# current_monitor_v1-2-1.net
KiCad netlist of a schematic drawn in EAGLE
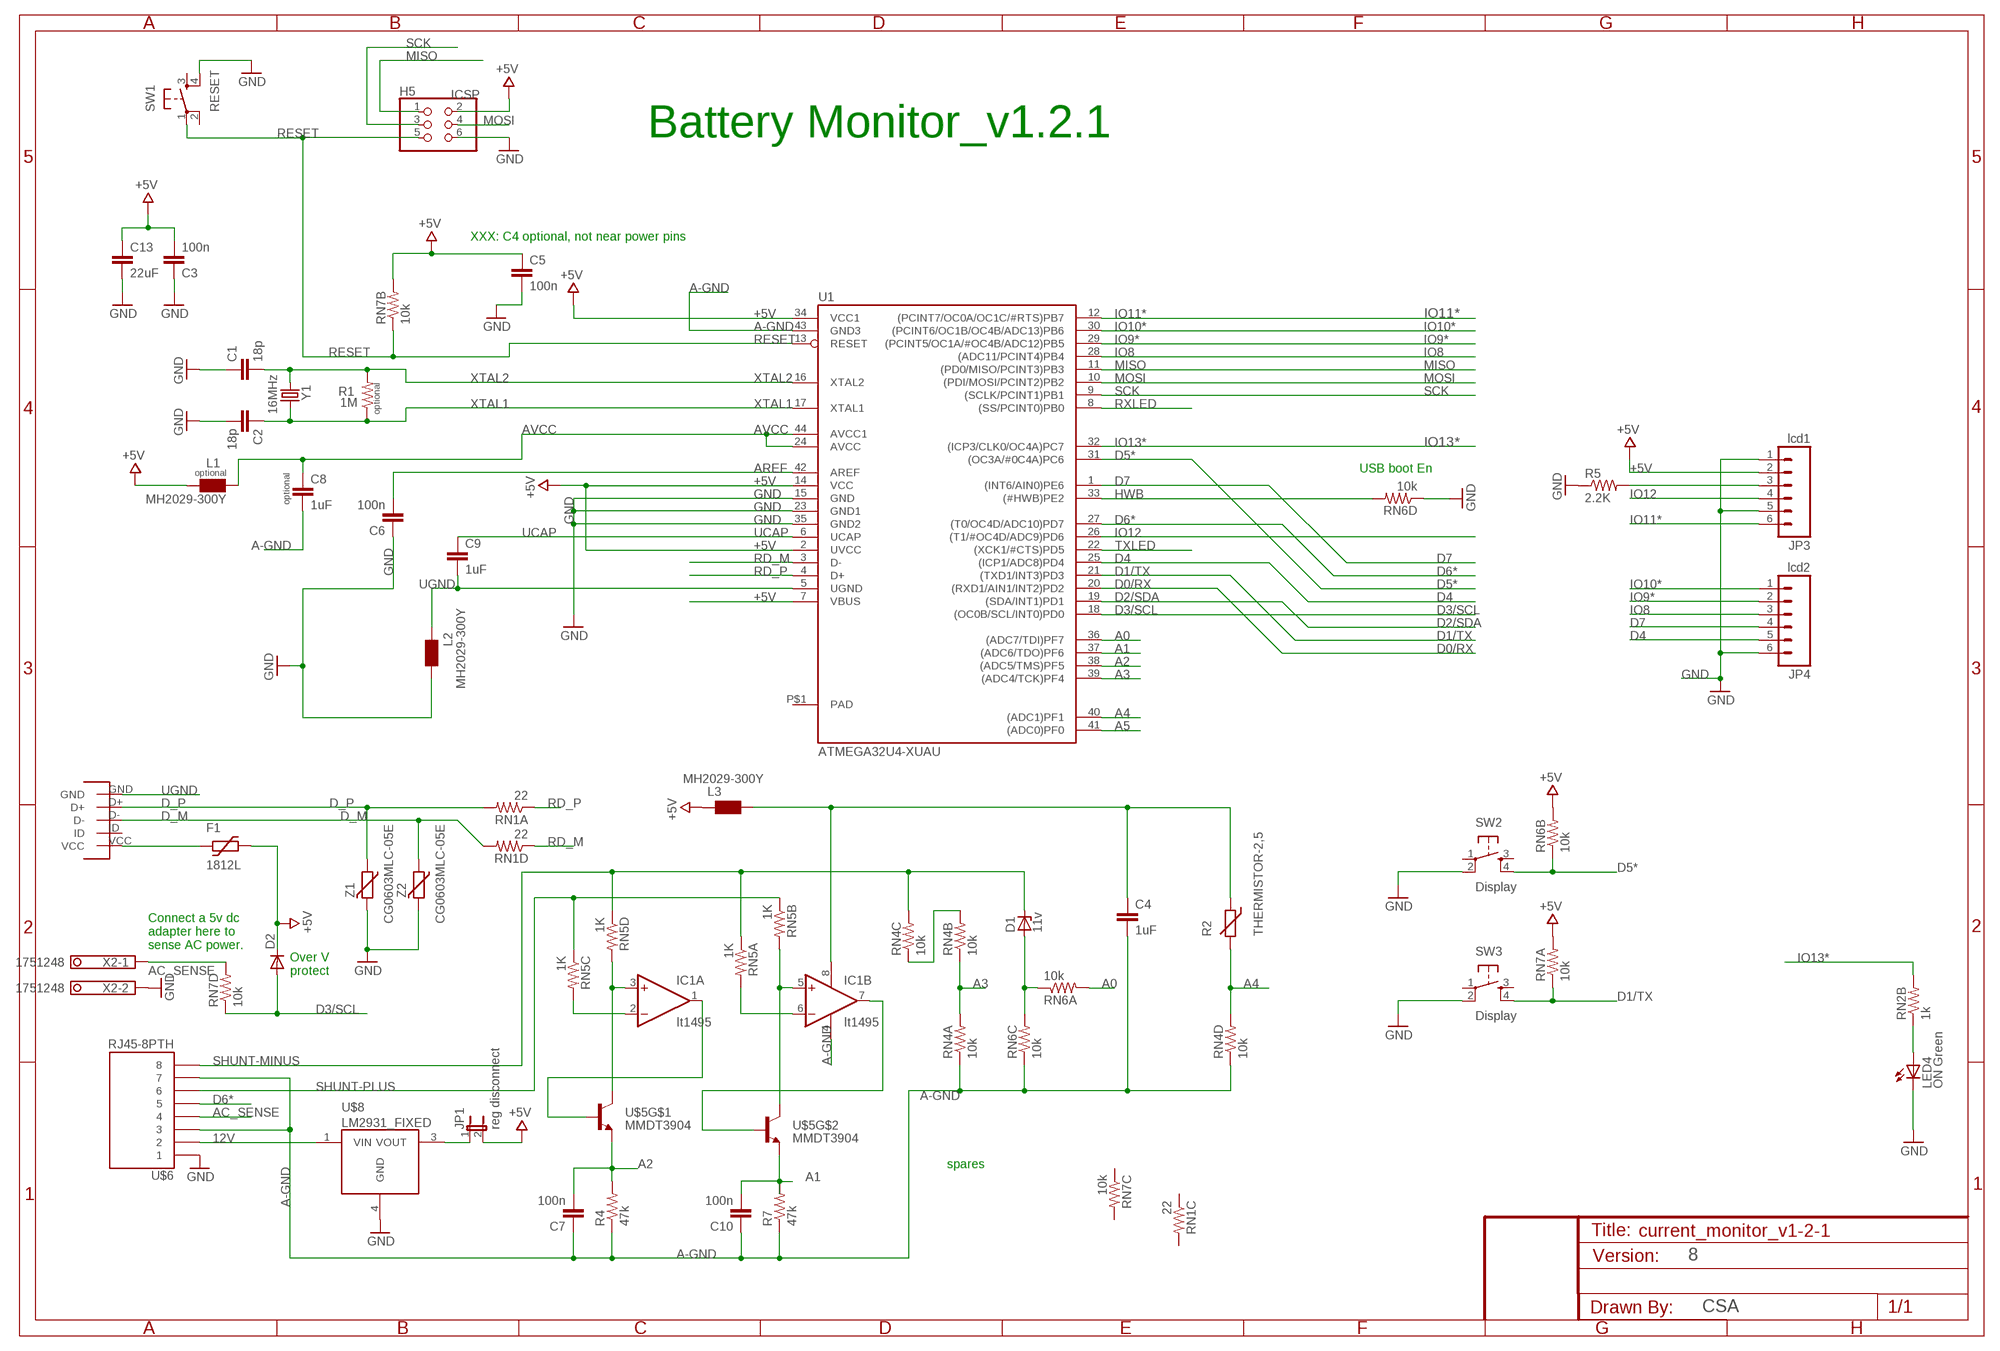
[diagram p0: schematic, sheet 1]

(export (version "E")
  (design (tool "Eeschema 10.0.6"))
  (components
    (comp (ref "C1")
      (value "18p")
      (footprint "eagle-import:0805")
      (libsource (lib "eagle-import") (part "CAP0805"))
    )
    (comp (ref "C2")
      (value "18p")
      (footprint "eagle-import:0805")
      (libsource (lib "eagle-import") (part "CAP0805"))
    )
    (comp (ref "C3")
      (value "100n")
      (footprint "eagle-import:0805")
      (libsource (lib "eagle-import") (part "CAP0805"))
    )
    (comp (ref "C4")
      (value "1uF")
      (footprint "eagle-import:0805")
      (libsource (lib "eagle-import") (part "CAP0805"))
    )
    (comp (ref "C5")
      (value "100n")
      (footprint "eagle-import:0805")
      (libsource (lib "eagle-import") (part "CAP0805"))
    )
    (comp (ref "C6")
      (value "100n")
      (footprint "eagle-import:0805")
      (libsource (lib "eagle-import") (part "CAP0805"))
    )
    (comp (ref "C7")
      (value "100n")
      (footprint "eagle-import:0805")
      (libsource (lib "eagle-import") (part "CAP0805"))
    )
    (comp (ref "C8")
      (value "1uF")
      (footprint "eagle-import:0805")
      (libsource (lib "eagle-import") (part "CAP0805"))
    )
    (comp (ref "C9")
      (value "1uF")
      (footprint "eagle-import:0805")
      (libsource (lib "eagle-import") (part "CAP0805"))
    )
    (comp (ref "C10")
      (value "100n")
      (footprint "eagle-import:0805")
      (libsource (lib "eagle-import") (part "CAP0805"))
    )
    (comp (ref "C13")
      (value "22uF")
      (footprint "eagle-import:1206")
      (libsource (lib "eagle-import") (part "CAP1206"))
    )
    (comp (ref "D1")
      (value "11v")
      (footprint "eagle-import:ZDIO-5")
      (libsource (lib "eagle-import") (part "ZENER-DIODEZD-5"))
    )
    (comp (ref "D2")
      (value "DIODESMA")
      (footprint "eagle-import:SMA-DIODE")
      (libsource (lib "eagle-import") (part "DIODESMA"))
    )
    (comp (ref "F1")
      (value "1812L")
      (footprint "eagle-import:1812L")
      (libsource (lib "eagle-import") (part "1812L"))
    )
    (comp (ref "H5")
      (value "ICSP")
      (footprint "eagle-import:2X03")
      (libsource (lib "eagle-import") (part "PINHD-2X3"))
    )
    (comp (ref "IC1")
      (value "lt1495")
      (footprint "eagle-import:SO08")
      (libsource (lib "eagle-import") (part "4558DLM"))
    )
    (comp (ref "JP1")
      (value "reg disconnect")
      (footprint "eagle-import:1X02_LOCK")
      (libsource (lib "eagle-import") (part "JUMPER-2-OLDPTH_LOCK"))
    )
    (comp (ref "JP3")
      (value "lcd1")
      (footprint "eagle-import:1X06_FEMALE_LOCK.010")
      (libsource (lib "eagle-import") (part "M06FEMALE_LOCK"))
    )
    (comp (ref "JP4")
      (value "lcd2")
      (footprint "eagle-import:1X06_FEMALE_LOCK.010")
      (libsource (lib "eagle-import") (part "M06FEMALE_LOCK"))
    )
    (comp (ref "L1")
      (value "MH2029-300Y")
      (footprint "eagle-import:0805")
      (libsource (lib "eagle-import") (part "WE-CBF_0805"))
    )
    (comp (ref "L2")
      (value "MH2029-300Y")
      (footprint "eagle-import:0805")
      (libsource (lib "eagle-import") (part "WE-CBF_0805"))
    )
    (comp (ref "L3")
      (value "MH2029-300Y")
      (footprint "eagle-import:0805")
      (libsource (lib "eagle-import") (part "WE-CBF_0805"))
    )
    (comp (ref "LED4")
      (value "ON Green")
      (footprint "eagle-import:LED0805")
      (libsource (lib "eagle-import") (part "LED0805"))
    )
    (comp (ref "R1")
      (value "1M")
      (footprint "eagle-import:0805")
      (libsource (lib "eagle-import") (part "RESISTOR0805-RES"))
    )
    (comp (ref "R2")
      (value "THERMISTOR-2,5")
      (footprint "eagle-import:RS-2,5")
      (libsource (lib "eagle-import") (part "THERMISTOR-2,5"))
    )
    (comp (ref "R4")
      (value "47k")
      (footprint "eagle-import:0805")
      (libsource (lib "eagle-import") (part "RESISTOR0805-RES"))
    )
    (comp (ref "R5")
      (value "2.2K")
      (footprint "eagle-import:0805")
      (libsource (lib "eagle-import") (part "RESISTOR0805-RES"))
    )
    (comp (ref "R7")
      (value "47k")
      (footprint "eagle-import:0805")
      (libsource (lib "eagle-import") (part "RESISTOR0805-RES"))
    )
    (comp (ref "RN1")
      (value "22")
      (footprint "eagle-import:CRA06S")
      (libsource (lib "eagle-import") (part "RESISTOR-ARRAYCRA06S"))
    )
    (comp (ref "RN2")
      (value "1k")
      (footprint "eagle-import:CRA06S")
      (libsource (lib "eagle-import") (part "RESISTOR-ARRAYCRA06S"))
    )
    (comp (ref "RN4")
      (value "10k")
      (footprint "eagle-import:CRA06S")
      (libsource (lib "eagle-import") (part "RESISTOR-ARRAYCRA06S"))
    )
    (comp (ref "RN5")
      (value "1K")
      (footprint "eagle-import:CRA06S")
      (libsource (lib "eagle-import") (part "RESISTOR-ARRAYCRA06S"))
    )
    (comp (ref "RN6")
      (value "10k")
      (footprint "eagle-import:CRA06S")
      (libsource (lib "eagle-import") (part "RESISTOR-ARRAYCRA06S"))
    )
    (comp (ref "RN7")
      (value "10k")
      (footprint "eagle-import:CRA06S")
      (libsource (lib "eagle-import") (part "RESISTOR-ARRAYCRA06S"))
    )
    (comp (ref "SW1")
      (value "RESET")
      (footprint "eagle-import:TACTILE-PTH")
      (libsource (lib "eagle-import") (part "TAC_SWITCHPTH"))
    )
    (comp (ref "SW2")
      (value "Display")
      (footprint "eagle-import:TACTILE-PTH")
      (libsource (lib "eagle-import") (part "TAC_SWITCHPTH"))
    )
    (comp (ref "SW3")
      (value "Display")
      (footprint "eagle-import:TACTILE-PTH")
      (libsource (lib "eagle-import") (part "TAC_SWITCHPTH"))
    )
    (comp (ref "U$5")
      (value "MMDT3904")
      (footprint "eagle-import:SOT363")
      (libsource (lib "eagle-import") (part "MMDT3904"))
    )
    (comp (ref "U$6")
      (value "RJ45-8PTH")
      (footprint "eagle-import:RJ45-8")
      (libsource (lib "eagle-import") (part "RJ45-8PTH"))
    )
    (comp (ref "U$8")
      (value "LM2931_FIXED")
      (footprint "eagle-import:DPAK")
      (libsource (lib "eagle-import") (part "LM2931_FIXED"))
    )
    (comp (ref "U$16")
      (value "USB-MICRO-B-DIGIKEY")
      (footprint "eagle-import:USB-MICRO-B-DIGIKEY")
      (libsource (lib "eagle-import") (part "USB-MICRO-B-DIGIKEY"))
    )
    (comp (ref "U1")
      (value "ATMEGA32U4-XUAU")
      (footprint "eagle-import:TQFP44-PAD")
      (libsource (lib "eagle-import") (part "ATMEGA32U4-XUAU"))
    )
    (comp (ref "X2")
      (value "1751248")
      (footprint "eagle-import:1751248")
      (libsource (lib "eagle-import") (part "1751248"))
    )
    (comp (ref "Y1")
      (value "16MHz")
      (footprint "eagle-import:HC49US")
      (libsource (lib "eagle-import") (part "CRYSTALHC49US"))
    )
    (comp (ref "Z1")
      (value "CG0603MLC-05E")
      (footprint "eagle-import:CT_CN0603")
      (libsource (lib "eagle-import") (part "VARISTORCN0603"))
    )
    (comp (ref "Z2")
      (value "CG0603MLC-05E")
      (footprint "eagle-import:CT_CN0603")
      (libsource (lib "eagle-import") (part "VARISTORCN0603"))
    )
  )
  (nets
    (net (code "1") (name "+5V") (class "Default")
      (node (ref "C13") (pin "1") (pinfunction "1_1") (pintype "passive"))
      (node (ref "C3") (pin "2") (pinfunction "2_2") (pintype "passive"))
      (node (ref "C5") (pin "1") (pinfunction "1_1") (pintype "passive"))
      (node (ref "D2") (pin "C") (pinfunction "C_C") (pintype "passive"))
      (node (ref "F1") (pin "P$2") (pinfunction "2_P$2") (pintype "passive"))
      (node (ref "H5") (pin "2") (pinfunction "2_2") (pintype "passive"))
      (node (ref "JP1") (pin "2") (pinfunction "2_2") (pintype "passive"))
      (node (ref "JP3") (pin "2") (pinfunction "2_2") (pintype "passive"))
      (node (ref "L1") (pin "1") (pinfunction "1_1") (pintype "passive"))
      (node (ref "L3") (pin "1") (pinfunction "1_1") (pintype "passive"))
      (node (ref "RN6") (pin "7") (pinfunction "2_7") (pintype "passive"))
      (node (ref "RN7") (pin "7") (pinfunction "2_7") (pintype "passive"))
      (node (ref "RN7") (pin "8") (pinfunction "2_8") (pintype "passive"))
      (node (ref "U1") (pin "14") (pinfunction "VCC_14") (pintype "power_in"))
      (node (ref "U1") (pin "2") (pinfunction "UVCC_2") (pintype "power_in"))
      (node (ref "U1") (pin "34") (pinfunction "VCC1_34") (pintype "power_in"))
      (node (ref "U1") (pin "7") (pinfunction "VBUS_7") (pintype "input"))
    )
    (net (code "2") (name "/12V") (class "Default")
      (node (ref "U$6") (pin "2") (pinfunction "2_2") (pintype "bidirectional"))
      (node (ref "U$8") (pin "1") (pinfunction "VIN_1") (pintype "bidirectional"))
    )
    (net (code "3") (name "/A-GND") (class "Default")
      (node (ref "C10") (pin "1") (pinfunction "1_1") (pintype "passive"))
      (node (ref "C4") (pin "2") (pinfunction "2_2") (pintype "passive"))
      (node (ref "C7") (pin "1") (pinfunction "1_1") (pintype "passive"))
      (node (ref "C8") (pin "2") (pinfunction "2_2") (pintype "passive"))
      (node (ref "IC1") (pin "4") (pinfunction "V-_4") (pintype "power_in"))
      (node (ref "R4") (pin "1") (pinfunction "1_1") (pintype "passive"))
      (node (ref "R7") (pin "1") (pinfunction "1_1") (pintype "passive"))
      (node (ref "RN4") (pin "1") (pinfunction "1_1") (pintype "passive"))
      (node (ref "RN4") (pin "4") (pinfunction "1_4") (pintype "passive"))
      (node (ref "RN6") (pin "3") (pinfunction "1_3") (pintype "passive"))
      (node (ref "U$6") (pin "3") (pinfunction "3_3") (pintype "bidirectional"))
      (node (ref "U$6") (pin "7") (pinfunction "7_7") (pintype "bidirectional"))
      (node (ref "U1") (pin "43") (pinfunction "GND3_43") (pintype "power_in"))
    )
    (net (code "4") (name "/A0") (class "Default")
      (node (ref "RN6") (pin "8") (pinfunction "2_8") (pintype "passive"))
      (node (ref "U1") (pin "36") (pinfunction "(ADC7/TDI)PF7_36") (pintype "bidirectional"))
    )
    (net (code "5") (name "/A1") (class "Default")
      (node (ref "C10") (pin "2") (pinfunction "2_2") (pintype "passive"))
      (node (ref "R7") (pin "2") (pinfunction "2_2") (pintype "passive"))
      (node (ref "U$5") (pin "1") (pinfunction "E_1") (pintype "passive"))
      (node (ref "U1") (pin "37") (pinfunction "(ADC6/TDO)PF6_37") (pintype "bidirectional"))
    )
    (net (code "6") (name "/A2") (class "Default")
      (node (ref "C7") (pin "2") (pinfunction "2_2") (pintype "passive"))
      (node (ref "R4") (pin "2") (pinfunction "2_2") (pintype "passive"))
      (node (ref "U$5") (pin "4") (pinfunction "E_4") (pintype "passive"))
      (node (ref "U1") (pin "38") (pinfunction "(ADC5/TMS)PF5_38") (pintype "bidirectional"))
    )
    (net (code "7") (name "/A3") (class "Default")
      (node (ref "RN4") (pin "2") (pinfunction "1_2") (pintype "passive"))
      (node (ref "RN4") (pin "8") (pinfunction "2_8") (pintype "passive"))
      (node (ref "U1") (pin "39") (pinfunction "(ADC4/TCK)PF4_39") (pintype "bidirectional"))
    )
    (net (code "8") (name "/A4") (class "Default")
      (node (ref "R2") (pin "2") (pinfunction "2_2") (pintype "passive"))
      (node (ref "RN4") (pin "5") (pinfunction "2_5") (pintype "passive"))
      (node (ref "U1") (pin "40") (pinfunction "(ADC1)PF1_40") (pintype "bidirectional"))
    )
    (net (code "9") (name "/A5") (class "Default")
      (node (ref "U1") (pin "41") (pinfunction "(ADC0)PF0_41") (pintype "bidirectional"))
    )
    (net (code "10") (name "/AC_SENSE") (class "Default")
      (node (ref "RN7") (pin "5") (pinfunction "2_5") (pintype "passive"))
      (node (ref "U$6") (pin "4") (pinfunction "4_4") (pintype "bidirectional"))
      (node (ref "X2") (pin "1") (pinfunction "K_1") (pintype "passive"))
    )
    (net (code "11") (name "/AREF") (class "Default")
      (node (ref "C6") (pin "2") (pinfunction "2_2") (pintype "passive"))
      (node (ref "U1") (pin "42") (pinfunction "AREF_42") (pintype "power_in"))
    )
    (net (code "12") (name "/AVCC") (class "Default")
      (node (ref "C8") (pin "1") (pinfunction "1_1") (pintype "passive"))
      (node (ref "L1") (pin "2") (pinfunction "2_2") (pintype "passive"))
      (node (ref "U1") (pin "24") (pinfunction "AVCC_24") (pintype "power_in"))
      (node (ref "U1") (pin "44") (pinfunction "AVCC1_44") (pintype "power_in"))
    )
    (net (code "13") (name "/D0{slash}RX") (class "Default")
      (node (ref "U1") (pin "20") (pinfunction "(RXD1/AIN1/INT2)PD2_20") (pintype "bidirectional"))
    )
    (net (code "14") (name "/D1{slash}TX") (class "Default")
      (node (ref "RN7") (pin "1") (pinfunction "1_1") (pintype "passive"))
      (node (ref "SW3") (pin "4") (pinfunction "4_4") (pintype "passive"))
      (node (ref "U1") (pin "21") (pinfunction "(TXD1/INT3)PD3_21") (pintype "bidirectional"))
    )
    (net (code "15") (name "/D2{slash}SDA") (class "Default")
      (node (ref "U1") (pin "19") (pinfunction "(SDA/INT1)PD1_19") (pintype "bidirectional"))
    )
    (net (code "16") (name "/D3{slash}SCL") (class "Default")
      (node (ref "D2") (pin "A") (pinfunction "A_A") (pintype "passive"))
      (node (ref "RN7") (pin "4") (pinfunction "1_4") (pintype "passive"))
      (node (ref "U1") (pin "18") (pinfunction "(OC0B/SCL/INT0)PD0_18") (pintype "bidirectional"))
    )
    (net (code "17") (name "/D4") (class "Default")
      (node (ref "JP4") (pin "5") (pinfunction "5_5") (pintype "passive"))
      (node (ref "U1") (pin "25") (pinfunction "(ICP1/ADC8)PD4_25") (pintype "bidirectional"))
    )
    (net (code "18") (name "/D5*") (class "Default")
      (node (ref "RN6") (pin "2") (pinfunction "1_2") (pintype "passive"))
      (node (ref "SW2") (pin "4") (pinfunction "4_4") (pintype "passive"))
      (node (ref "U1") (pin "31") (pinfunction "(OC3A/#0C4A)PC6_31") (pintype "bidirectional"))
    )
    (net (code "19") (name "/D6*") (class "Default")
      (node (ref "U$6") (pin "5") (pinfunction "5_5") (pintype "bidirectional"))
      (node (ref "U1") (pin "27") (pinfunction "(T0/OC4D/ADC10)PD7_27") (pintype "bidirectional"))
    )
    (net (code "20") (name "/D7") (class "Default")
      (node (ref "JP4") (pin "4") (pinfunction "4_4") (pintype "passive"))
      (node (ref "U1") (pin "1") (pinfunction "(INT6/AIN0)PE6_1") (pintype "bidirectional"))
    )
    (net (code "21") (name "/D_M") (class "Default")
      (node (ref "RN1") (pin "5") (pinfunction "2_5") (pintype "passive"))
      (node (ref "U$16") (pin "D-") (pinfunction "D-_D-") (pintype "bidirectional"))
      (node (ref "Z2") (pin "1") (pinfunction "1_1") (pintype "passive"))
    )
    (net (code "22") (name "/D_P") (class "Default")
      (node (ref "RN1") (pin "8") (pinfunction "2_8") (pintype "passive"))
      (node (ref "U$16") (pin "D+") (pinfunction "D+_D+") (pintype "bidirectional"))
      (node (ref "Z1") (pin "1") (pinfunction "1_1") (pintype "passive"))
    )
    (net (code "23") (name "/HWB") (class "Default")
      (node (ref "RN6") (pin "5") (pinfunction "2_5") (pintype "passive"))
      (node (ref "U1") (pin "33") (pinfunction "(#HWB)PE2_33") (pintype "bidirectional"))
    )
    (net (code "24") (name "/IO8") (class "Default")
      (node (ref "JP4") (pin "3") (pinfunction "3_3") (pintype "passive"))
      (node (ref "U1") (pin "28") (pinfunction "(ADC11/PCINT4)PB4_28") (pintype "bidirectional"))
    )
    (net (code "25") (name "/IO9*") (class "Default")
      (node (ref "JP4") (pin "2") (pinfunction "2_2") (pintype "passive"))
      (node (ref "U1") (pin "29") (pinfunction "(PCINT5/OC1A/#OC4B/ADC12)PB5_29") (pintype "bidirectional"))
    )
    (net (code "26") (name "/IO10*") (class "Default")
      (node (ref "JP4") (pin "1") (pinfunction "1_1") (pintype "passive"))
      (node (ref "U1") (pin "30") (pinfunction "(PCINT6/OC1B/OC4B/ADC13)PB6_30") (pintype "bidirectional"))
    )
    (net (code "27") (name "/IO11*") (class "Default")
      (node (ref "JP3") (pin "6") (pinfunction "6_6") (pintype "passive"))
      (node (ref "U1") (pin "12") (pinfunction "(PCINT7/OC0A/OC1C/#RTS)PB7_12") (pintype "bidirectional"))
    )
    (net (code "28") (name "/IO12") (class "Default")
      (node (ref "JP3") (pin "4") (pinfunction "4_4") (pintype "passive"))
      (node (ref "U1") (pin "26") (pinfunction "(T1/#OC4D/ADC9)PD6_26") (pintype "bidirectional"))
    )
    (net (code "29") (name "/IO13*") (class "Default")
      (node (ref "RN2") (pin "7") (pinfunction "2_7") (pintype "passive"))
      (node (ref "U1") (pin "32") (pinfunction "(ICP3/CLK0/OC4A)PC7_32") (pintype "bidirectional"))
    )
    (net (code "30") (name "/MISO") (class "Default")
      (node (ref "H5") (pin "1") (pinfunction "1_1") (pintype "passive"))
      (node (ref "U1") (pin "11") (pinfunction "(PD0/MISO/PCINT3)PB3_11") (pintype "bidirectional"))
    )
    (net (code "31") (name "/MOSI") (class "Default")
      (node (ref "H5") (pin "4") (pinfunction "4_4") (pintype "passive"))
      (node (ref "U1") (pin "10") (pinfunction "(PDI/MOSI/PCINT2)PB2_10") (pintype "bidirectional"))
    )
    (net (code "32") (name "/PAD") (class "Default")
      (node (ref "U1") (pin "P$1") (pinfunction "PAD_P$1") (pintype "power_in"))
    )
    (net (code "33") (name "/RD_M") (class "Default")
      (node (ref "RN1") (pin "4") (pinfunction "1_4") (pintype "passive"))
      (node (ref "U1") (pin "3") (pinfunction "D-_3") (pintype "bidirectional"))
    )
    (net (code "34") (name "/RD_P") (class "Default")
      (node (ref "RN1") (pin "1") (pinfunction "1_1") (pintype "passive"))
      (node (ref "U1") (pin "4") (pinfunction "D+_4") (pintype "bidirectional"))
    )
    (net (code "35") (name "/RESET") (class "Default")
      (node (ref "H5") (pin "5") (pinfunction "5_5") (pintype "passive"))
      (node (ref "RN7") (pin "2") (pinfunction "1_2") (pintype "passive"))
      (node (ref "SW1") (pin "1") (pinfunction "1_1") (pintype "passive"))
      (node (ref "U1") (pin "13") (pinfunction "RESET_13") (pintype "input"))
    )
    (net (code "36") (name "/RXLED") (class "Default")
      (node (ref "U1") (pin "8") (pinfunction "(SS/PCINT0)PB0_8") (pintype "bidirectional"))
    )
    (net (code "37") (name "/SCK") (class "Default")
      (node (ref "H5") (pin "3") (pinfunction "3_3") (pintype "passive"))
      (node (ref "U1") (pin "9") (pinfunction "(SCLK/PCINT1)PB1_9") (pintype "bidirectional"))
    )
    (net (code "38") (name "/SHUNT-MINUS") (class "Default")
      (node (ref "D1") (pin "C") (pinfunction "C_C") (pintype "passive"))
      (node (ref "RN4") (pin "6") (pinfunction "2_6") (pintype "passive"))
      (node (ref "RN5") (pin "1") (pinfunction "1_1") (pintype "passive"))
      (node (ref "RN5") (pin "4") (pinfunction "1_4") (pintype "passive"))
      (node (ref "U$6") (pin "8") (pinfunction "8_8") (pintype "bidirectional"))
    )
    (net (code "39") (name "/SHUNT-PLUS") (class "Default")
      (node (ref "RN5") (pin "2") (pinfunction "1_2") (pintype "passive"))
      (node (ref "RN5") (pin "3") (pinfunction "1_3") (pintype "passive"))
      (node (ref "U$6") (pin "6") (pinfunction "6_6") (pintype "bidirectional"))
    )
    (net (code "40") (name "/TXLED") (class "Default")
      (node (ref "U1") (pin "22") (pinfunction "(XCK1/#CTS)PD5_22") (pintype "bidirectional"))
    )
    (net (code "41") (name "/UCAP") (class "Default")
      (node (ref "C9") (pin "1") (pinfunction "1_1") (pintype "passive"))
      (node (ref "U1") (pin "6") (pinfunction "UCAP_6") (pintype "passive"))
    )
    (net (code "42") (name "/UGND") (class "Default")
      (node (ref "C9") (pin "2") (pinfunction "2_2") (pintype "passive"))
      (node (ref "L2") (pin "1") (pinfunction "1_1") (pintype "passive"))
      (node (ref "U$16") (pin "GND") (pinfunction "GND_GND") (pintype "bidirectional"))
      (node (ref "U1") (pin "5") (pinfunction "UGND_5") (pintype "power_in"))
    )
    (net (code "43") (name "/XTAL1") (class "Default")
      (node (ref "C2") (pin "1") (pinfunction "1_1") (pintype "passive"))
      (node (ref "R1") (pin "1") (pinfunction "1_1") (pintype "passive"))
      (node (ref "U1") (pin "17") (pinfunction "XTAL1_17") (pintype "bidirectional"))
      (node (ref "Y1") (pin "2") (pinfunction "2_2") (pintype "passive"))
    )
    (net (code "44") (name "/XTAL2") (class "Default")
      (node (ref "C1") (pin "2") (pinfunction "2_2") (pintype "passive"))
      (node (ref "R1") (pin "2") (pinfunction "2_2") (pintype "passive"))
      (node (ref "U1") (pin "16") (pinfunction "XTAL2_16") (pintype "bidirectional"))
      (node (ref "Y1") (pin "1") (pinfunction "1_1") (pintype "passive"))
    )
    (net (code "45") (name "GND") (class "Default")
      (node (ref "C1") (pin "1") (pinfunction "1_1") (pintype "passive"))
      (node (ref "C13") (pin "2") (pinfunction "2_2") (pintype "passive"))
      (node (ref "C2") (pin "2") (pinfunction "2_2") (pintype "passive"))
      (node (ref "C3") (pin "1") (pinfunction "1_1") (pintype "passive"))
      (node (ref "C5") (pin "2") (pinfunction "2_2") (pintype "passive"))
      (node (ref "C6") (pin "1") (pinfunction "1_1") (pintype "passive"))
      (node (ref "H5") (pin "6") (pinfunction "6_6") (pintype "passive"))
      (node (ref "JP3") (pin "1") (pinfunction "1_1") (pintype "passive"))
      (node (ref "JP3") (pin "5") (pinfunction "5_5") (pintype "passive"))
      (node (ref "JP4") (pin "6") (pinfunction "6_6") (pintype "passive"))
      (node (ref "L2") (pin "2") (pinfunction "2_2") (pintype "passive"))
      (node (ref "LED4") (pin "C") (pinfunction "C_C") (pintype "passive"))
      (node (ref "R5") (pin "1") (pinfunction "1_1") (pintype "passive"))
      (node (ref "RN6") (pin "4") (pinfunction "1_4") (pintype "passive"))
      (node (ref "SW1") (pin "4") (pinfunction "4_4") (pintype "passive"))
      (node (ref "SW2") (pin "2") (pinfunction "2_2") (pintype "passive"))
      (node (ref "SW3") (pin "2") (pinfunction "2_2") (pintype "passive"))
      (node (ref "U$6") (pin "1") (pinfunction "1_1") (pintype "bidirectional"))
      (node (ref "U$8") (pin "4") (pinfunction "GND_4") (pintype "bidirectional"))
      (node (ref "U1") (pin "15") (pinfunction "GND_15") (pintype "power_in"))
      (node (ref "U1") (pin "23") (pinfunction "GND1_23") (pintype "power_in"))
      (node (ref "U1") (pin "35") (pinfunction "GND2_35") (pintype "power_in"))
      (node (ref "X2") (pin "2") (pinfunction "K_2") (pintype "passive"))
      (node (ref "Z1") (pin "2") (pinfunction "2_2") (pintype "passive"))
      (node (ref "Z2") (pin "2") (pinfunction "2_2") (pintype "passive"))
    )
    (net (code "46") (name "Net-(F1-1)") (class "Default")
      (node (ref "F1") (pin "P$1") (pinfunction "1_P$1") (pintype "passive"))
      (node (ref "U$16") (pin "VCC") (pinfunction "VCC_VCC") (pintype "bidirectional"))
    )
    (net (code "47") (name "Net-(IC1A-+IN)") (class "Default")
      (node (ref "IC1") (pin "3") (pinfunction "+IN_3") (pintype "input"))
      (node (ref "RN5") (pin "5") (pinfunction "2_5") (pintype "passive"))
      (node (ref "U$5") (pin "3") (pinfunction "C_3") (pintype "passive"))
    )
    (net (code "48") (name "Net-(IC1A--IN)") (class "Default")
      (node (ref "IC1") (pin "2") (pinfunction "-IN_2") (pintype "input"))
      (node (ref "RN5") (pin "6") (pinfunction "2_6") (pintype "passive"))
    )
    (net (code "49") (name "Net-(IC1A-OUT)") (class "Default")
      (node (ref "IC1") (pin "1") (pinfunction "OUT_1") (pintype "output"))
      (node (ref "U$5") (pin "5") (pinfunction "B_5") (pintype "passive"))
    )
    (net (code "50") (name "Net-(IC1B-+IN)") (class "Default")
      (node (ref "IC1") (pin "5") (pinfunction "+IN_5") (pintype "input"))
      (node (ref "RN5") (pin "7") (pinfunction "2_7") (pintype "passive"))
      (node (ref "U$5") (pin "6") (pinfunction "C_6") (pintype "passive"))
    )
    (net (code "51") (name "Net-(IC1B--IN)") (class "Default")
      (node (ref "IC1") (pin "6") (pinfunction "-IN_6") (pintype "input"))
      (node (ref "RN5") (pin "8") (pinfunction "2_8") (pintype "passive"))
    )
    (net (code "52") (name "Net-(IC1B-OUT)") (class "Default")
      (node (ref "IC1") (pin "7") (pinfunction "OUT_7") (pintype "output"))
      (node (ref "U$5") (pin "2") (pinfunction "B_2") (pintype "passive"))
    )
    (net (code "53") (name "Net-(IC1C-V+)") (class "Default")
      (node (ref "C4") (pin "1") (pinfunction "1_1") (pintype "passive"))
      (node (ref "IC1") (pin "8") (pinfunction "V+_8") (pintype "power_in"))
      (node (ref "L3") (pin "2") (pinfunction "2_2") (pintype "passive"))
      (node (ref "R2") (pin "1") (pinfunction "1_1") (pintype "passive"))
    )
    (net (code "54") (name "Net-(JP3-Pad3)") (class "Default")
      (node (ref "JP3") (pin "3") (pinfunction "3_3") (pintype "passive"))
      (node (ref "R5") (pin "2") (pinfunction "2_2") (pintype "passive"))
    )
    (net (code "55") (name "Net-(RN2B-1)") (class "Default")
      (node (ref "LED4") (pin "A") (pinfunction "A_A") (pintype "passive"))
      (node (ref "RN2") (pin "2") (pinfunction "1_2") (pintype "passive"))
    )
    (net (code "56") (name "Net-(RN4B-2)") (class "Default")
      (node (ref "RN4") (pin "3") (pinfunction "1_3") (pintype "passive"))
      (node (ref "RN4") (pin "7") (pinfunction "2_7") (pintype "passive"))
    )
    (net (code "57") (name "Net-(RN6C-2)") (class "Default")
      (node (ref "D1") (pin "A") (pinfunction "A_A") (pintype "passive"))
      (node (ref "RN6") (pin "1") (pinfunction "1_1") (pintype "passive"))
      (node (ref "RN6") (pin "6") (pinfunction "2_6") (pintype "passive"))
    )
    (net (code "58") (name "Net-(U$8-VOUT)") (class "Default")
      (node (ref "JP1") (pin "1") (pinfunction "1_1") (pintype "passive"))
      (node (ref "U$8") (pin "3") (pinfunction "VOUT_3") (pintype "bidirectional"))
    )
    (net (code "59") (name "unconnected-(RN1C-1-Pad3)") (class "Default")
      (node (ref "RN1") (pin "3") (pinfunction "1_3") (pintype "passive"))
    )
    (net (code "60") (name "unconnected-(RN1C-2-Pad6)") (class "Default")
      (node (ref "RN1") (pin "6") (pinfunction "2_6") (pintype "passive"))
    )
    (net (code "61") (name "unconnected-(RN7C-1-Pad3)") (class "Default")
      (node (ref "RN7") (pin "3") (pinfunction "1_3") (pintype "passive"))
    )
    (net (code "62") (name "unconnected-(RN7C-2-Pad6)") (class "Default")
      (node (ref "RN7") (pin "6") (pinfunction "2_6") (pintype "passive"))
    )
    (net (code "63") (name "unconnected-(SW1-Pad2)") (class "Default")
      (node (ref "SW1") (pin "2") (pinfunction "2_2") (pintype "passive"))
    )
    (net (code "64") (name "unconnected-(SW1-Pad3)") (class "Default")
      (node (ref "SW1") (pin "3") (pinfunction "3_3") (pintype "passive"))
    )
    (net (code "65") (name "unconnected-(SW2-Pad1)") (class "Default")
      (node (ref "SW2") (pin "1") (pinfunction "1_1") (pintype "passive"))
    )
    (net (code "66") (name "unconnected-(SW2-Pad3)") (class "Default")
      (node (ref "SW2") (pin "3") (pinfunction "3_3") (pintype "passive"))
    )
    (net (code "67") (name "unconnected-(SW3-Pad1)") (class "Default")
      (node (ref "SW3") (pin "1") (pinfunction "1_1") (pintype "passive"))
    )
    (net (code "68") (name "unconnected-(SW3-Pad3)") (class "Default")
      (node (ref "SW3") (pin "3") (pinfunction "3_3") (pintype "passive"))
    )
    (net (code "69") (name "unconnected-(U$16-PadID)") (class "Default")
      (node (ref "U$16") (pin "ID") (pinfunction "ID_ID") (pintype "bidirectional"))
    )
  )
)
